# PillEndo-Proto_SW.net
KiCad netlist of a schematic drawn in EAGLE
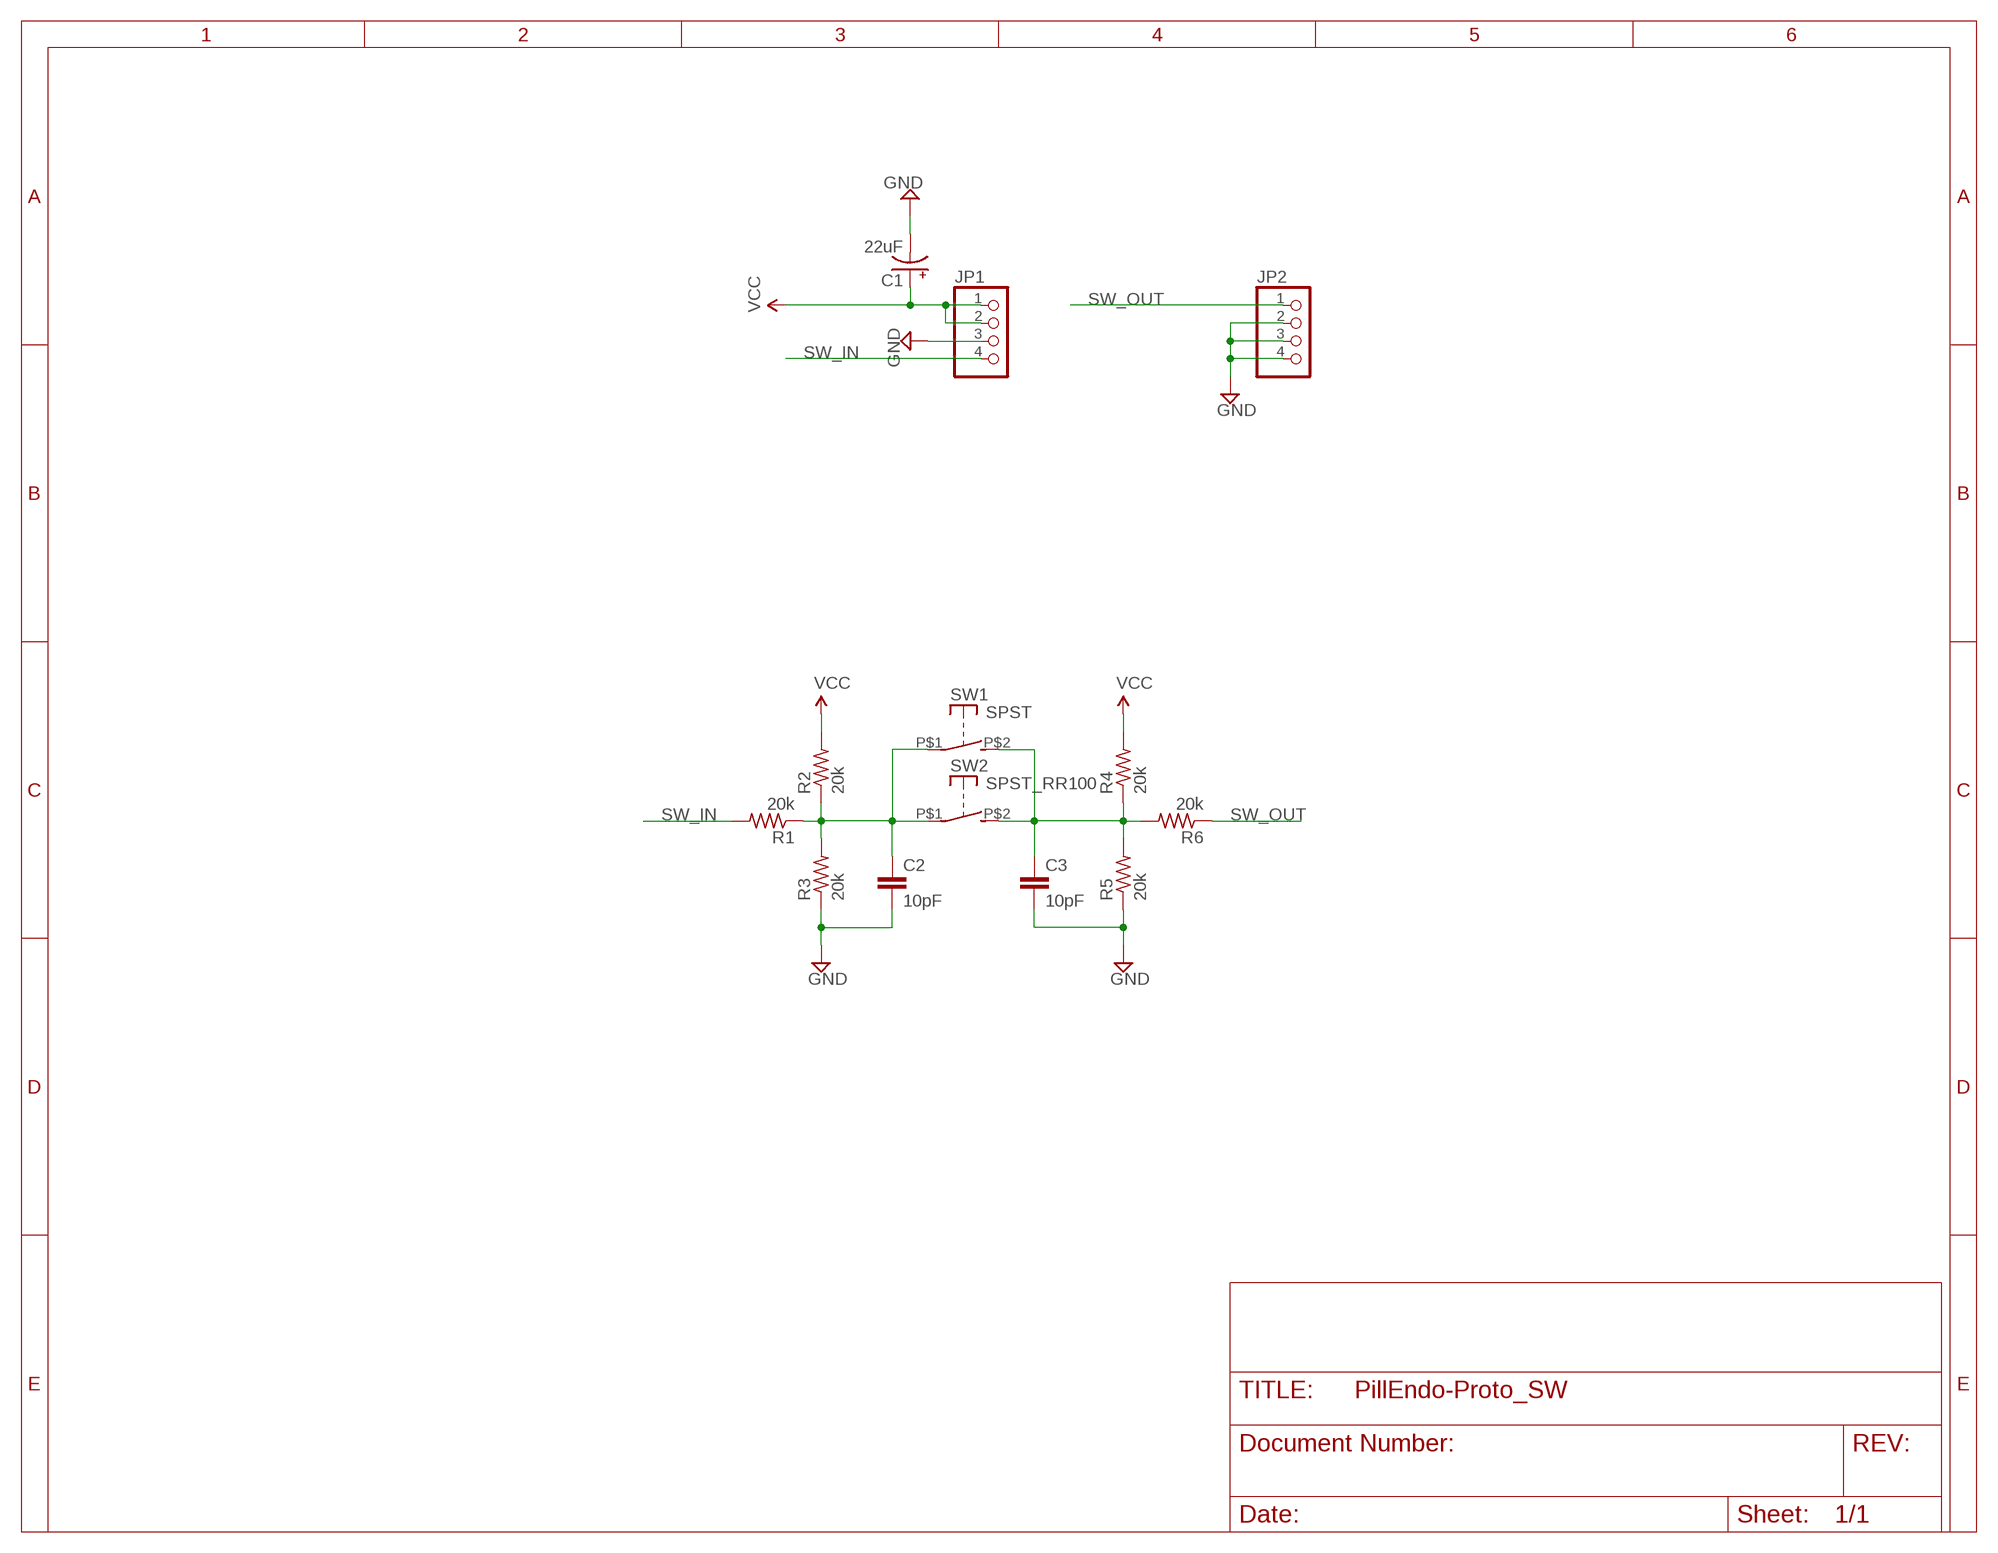
[diagram p0: schematic, sheet 1]

(export (version "E")
  (design (tool "Eeschema 10.0.6"))
  (components
    (comp (ref "C1")
      (value "22uF")
      (footprint "eagle-import:CT3216")
      (libsource (lib "eagle-import") (part "CPOL-USCT3216"))
    )
    (comp (ref "C2")
      (value "10pF")
      (footprint "eagle-import:C0603")
      (libsource (lib "eagle-import") (part "C-EUC0603"))
    )
    (comp (ref "C3")
      (value "10pF")
      (footprint "eagle-import:C0603")
      (libsource (lib "eagle-import") (part "C-EUC0603"))
    )
    (comp (ref "JP1")
      (value "PINHD-1X4")
      (footprint "eagle-import:1X04")
      (libsource (lib "eagle-import") (part "PINHD-1X4"))
    )
    (comp (ref "JP2")
      (value "PINHD-1X4")
      (footprint "eagle-import:1X04")
      (libsource (lib "eagle-import") (part "PINHD-1X4"))
    )
    (comp (ref "R1")
      (value "20k")
      (footprint "eagle-import:R0603")
      (libsource (lib "eagle-import") (part "R-US_R0603"))
    )
    (comp (ref "R2")
      (value "20k")
      (footprint "eagle-import:R0603")
      (libsource (lib "eagle-import") (part "R-US_R0603"))
    )
    (comp (ref "R3")
      (value "20k")
      (footprint "eagle-import:R0603")
      (libsource (lib "eagle-import") (part "R-US_R0603"))
    )
    (comp (ref "R4")
      (value "20k")
      (footprint "eagle-import:R0603")
      (libsource (lib "eagle-import") (part "R-US_R0603"))
    )
    (comp (ref "R5")
      (value "20k")
      (footprint "eagle-import:R0603")
      (libsource (lib "eagle-import") (part "R-US_R0603"))
    )
    (comp (ref "R6")
      (value "20k")
      (footprint "eagle-import:R0603")
      (libsource (lib "eagle-import") (part "R-US_R0603"))
    )
    (comp (ref "SW1")
      (value "SPST")
      (footprint "eagle-import:CT05")
      (libsource (lib "eagle-import") (part "SPST"))
    )
    (comp (ref "SW2")
      (value "SPST_RR100")
      (footprint "eagle-import:RR100")
      (libsource (lib "eagle-import") (part "SPST_RR100"))
    )
  )
  (nets
    (net (code "1") (name "/SW_IN") (class "Default")
      (node (ref "JP1") (pin "4") (pinfunction "4_4") (pintype "passive"))
      (node (ref "R1") (pin "2") (pinfunction "2_2") (pintype "passive"))
    )
    (net (code "2") (name "/SW_OUT") (class "Default")
      (node (ref "JP2") (pin "1") (pinfunction "1_1") (pintype "passive"))
      (node (ref "R6") (pin "1") (pinfunction "1_1") (pintype "passive"))
    )
    (net (code "3") (name "GND") (class "Default")
      (node (ref "C1") (pin "-") (pinfunction "-_-") (pintype "passive"))
      (node (ref "C2") (pin "2") (pinfunction "2_2") (pintype "passive"))
      (node (ref "C3") (pin "2") (pinfunction "2_2") (pintype "passive"))
      (node (ref "JP1") (pin "3") (pinfunction "3_3") (pintype "passive"))
      (node (ref "JP2") (pin "2") (pinfunction "2_2") (pintype "passive"))
      (node (ref "JP2") (pin "3") (pinfunction "3_3") (pintype "passive"))
      (node (ref "JP2") (pin "4") (pinfunction "4_4") (pintype "passive"))
      (node (ref "R3") (pin "1") (pinfunction "1_1") (pintype "passive"))
      (node (ref "R5") (pin "1") (pinfunction "1_1") (pintype "passive"))
    )
    (net (code "4") (name "Net-(SW1-P)") (class "Default")
      (node (ref "C2") (pin "1") (pinfunction "1_1") (pintype "passive"))
      (node (ref "R1") (pin "1") (pinfunction "1_1") (pintype "passive"))
      (node (ref "R2") (pin "1") (pinfunction "1_1") (pintype "passive"))
      (node (ref "R3") (pin "2") (pinfunction "2_2") (pintype "passive"))
      (node (ref "SW1") (pin "P$1") (pinfunction "P_P$1") (pintype "passive"))
      (node (ref "SW2") (pin "P$1") (pinfunction "P_P$1") (pintype "passive"))
    )
    (net (code "5") (name "Net-(SW1-S)") (class "Default")
      (node (ref "C3") (pin "1") (pinfunction "1_1") (pintype "passive"))
      (node (ref "R4") (pin "1") (pinfunction "1_1") (pintype "passive"))
      (node (ref "R5") (pin "2") (pinfunction "2_2") (pintype "passive"))
      (node (ref "R6") (pin "2") (pinfunction "2_2") (pintype "passive"))
      (node (ref "SW1") (pin "P$2") (pinfunction "S_P$2") (pintype "passive"))
      (node (ref "SW2") (pin "P$2") (pinfunction "S_P$2") (pintype "passive"))
    )
    (net (code "6") (name "VCC") (class "Default")
      (node (ref "C1") (pin "+") (pinfunction "+_+") (pintype "passive"))
      (node (ref "JP1") (pin "1") (pinfunction "1_1") (pintype "passive"))
      (node (ref "JP1") (pin "2") (pinfunction "2_2") (pintype "passive"))
      (node (ref "R2") (pin "2") (pinfunction "2_2") (pintype "passive"))
      (node (ref "R4") (pin "2") (pinfunction "2_2") (pintype "passive"))
    )
  )
)
